# Sch_Sh1.net
KiCad netlist of a schematic drawn in Altium Designer
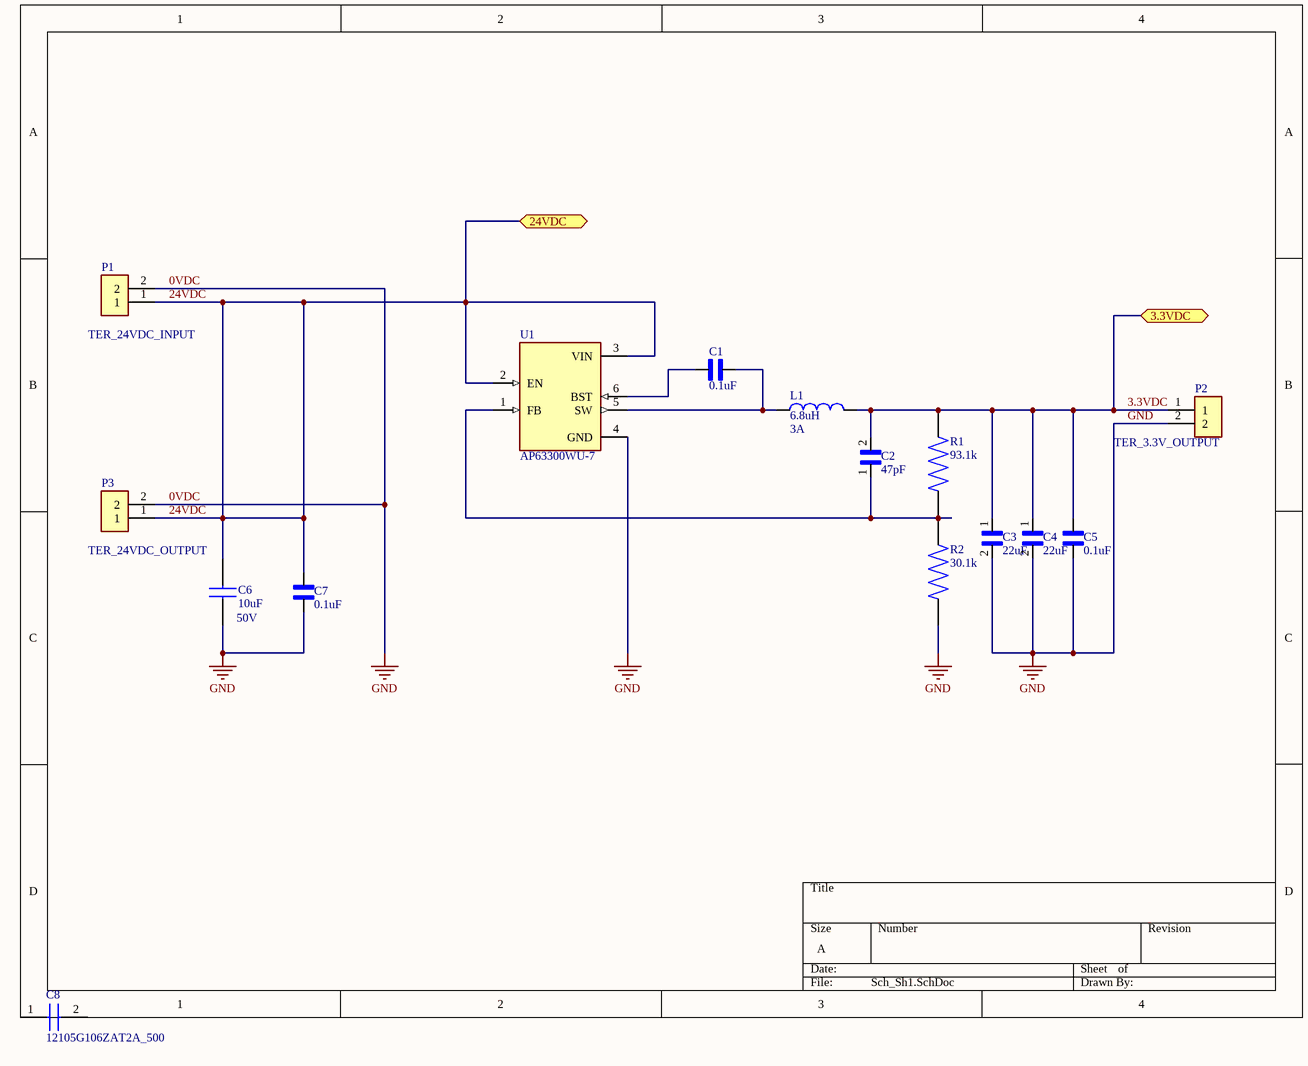
[diagram p0: Sch_Sh1.SchDoc]

(export (version "E")
  (design (tool "Eeschema 10.0.6"))
  (components
    (comp (ref "C1")
      (value "0.1uF")
      (footprint "WCAP-CSGP_885012205086")
      (fields (field (name "MP") "885012205086"))
      (libsource (lib "885012205086") (part "885012205086"))
    )
    (comp (ref "C2")
      (value "47pF")
      (footprint "SnapEDApcb:CAPC2012X145N")
      (description "SMD Capacitor X6S_EIA_ with Capacitance: 10uF Tol. 10%. Rated Voltage: 35Vdc")
      (fields (field (name "MP") "GRM21BC8YA106KE11L") (field (name "MF") "Murata"))
      (libsource (lib "SnapEDAsch") (part "GRM21BC8YA106KE11L"))
    )
    (comp (ref "C3")
      (value "22uF")
      (footprint "CAPC2012X140N")
      (description "22ÂµF Â±20% 25V Ceramic Capacitor X5R 0805 (2012 Metric)")
      (fields (field (name "MF") "Samsung") (field (name "DIGI-KEY_PART_NUMBER") "1276-2908-1-ND"))
      (libsource (lib "CL21A226MAQNNNE") (part "CL21A226MAQNNNE"))
    )
    (comp (ref "C4")
      (value "22uF")
      (footprint "CAPC2012X140N")
      (description "22ÂµF Â±20% 25V Ceramic Capacitor X5R 0805 (2012 Metric)")
      (fields (field (name "MF") "Samsung") (field (name "DIGI-KEY_PART_NUMBER") "1276-2908-1-ND"))
      (libsource (lib "CL21A226MAQNNNE") (part "CL21A226MAQNNNE"))
    )
    (comp (ref "C5")
      (value "0.1uF")
      (footprint "WCAP-CSGP_885012205086")
      (fields (field (name "MP") "885012205086"))
      (libsource (lib "") (part "885012205086_1"))
    )
    (comp (ref "C6")
      (value "10uF")
      (footprint "CAPC3225X290N")
      (description "CAP CER 10UF 50V Y5V 1210")
      (fields
        (field (name "MANUFACTURER_PART_NUMBER") "12105G106ZAT2A/500")
        (field (name "ALTIUM_UNNAMED_1") "50V")
      )
      (libsource (lib "12105G106ZAT2A_500") (part "12105G106ZAT2A_500"))
    )
    (comp (ref "C7")
      (value "0.1uF")
      (footprint "WCAP-CSGP_885012205086")
      (fields (field (name "MP") "885012205086"))
      (libsource (lib "") (part "885012205086_1"))
    )
    (comp (ref "C8")
      (value "12105G106ZAT2A_500")
      (footprint "SamacSys:CAPC3225X290N")
      (description "Capacitor")
      (fields (field (name "MANUFACTURER_PART_NUMBER") "12105G106ZAT2A/500"))
      (libsource (lib "*") (part "12105G106ZAT2A_500"))
    )
    (comp (ref "L1")
      (value "6.8uH")
      (footprint "INDC3225X170N")
      (description "INDUCTOR, 6.8UH, 1.05A, +20%")
      (fields (field (name "MP") "BRL3225T6R8M") (field (name "ALTIUM_UNNAMED_1") "3A"))
      (libsource (lib "BRL3225T6R8M") (part "BRL3225T6R8M"))
    )
    (comp (ref "P1")
      (value "282837-2")
      (footprint "TE_282837-2")
      (description "Connector Terminal Blocks Receptacle 2 Position 5.08mm Solder Straight Thru-Hole 13.5A/Contact")
      (fields (field (name "MF") "TE Connectivity") (field (name "COMMENT_1") "TER_24VDC_INPUT"))
      (libsource (lib "Con_TerminalBlock_2Pin_5.08mm") (part "282837-2"))
    )
    (comp (ref "P2")
      (value "282837-2")
      (footprint "TE_282837-2")
      (description "Connector Terminal Blocks Receptacle 2 Position 5.08mm Solder Straight Thru-Hole 13.5A/Contact")
      (fields (field (name "MF") "TE Connectivity") (field (name "COMMENT_1") "TER_3.3V_OUTPUT"))
      (libsource (lib "") (part "282837-2_1"))
    )
    (comp (ref "P3")
      (value "282837-2")
      (footprint "TE_282837-2")
      (description "Connector Terminal Blocks Receptacle 2 Position 5.08mm Solder Straight Thru-Hole 13.5A/Contact")
      (fields (field (name "MF") "TE Connectivity") (field (name "COMMENT_1") "TER_24VDC_OUTPUT"))
      (libsource (lib "Con_TerminalBlock_2Pin_5.08mm") (part "282837-2"))
    )
    (comp (ref "R1")
      (value "93.1k")
      (footprint "RESC1005X40N")
      (description "Res Thick Film 0402 93.1K Ohm 1% 1/16W Â±100ppm/Â°C Molded SMD Paper T/R")
      (fields (field (name "MP") "RC0402FR-0793K1L"))
      (libsource (lib "RC0402FR-0793K1L") (part "RC0402FR-0793K1L"))
    )
    (comp (ref "R2")
      (value "30.1k")
      (footprint "RES_ERJ2RKF3012X")
      (fields (field (name "MP") "ERJ2RKF3012X"))
      (libsource (lib "ERJ2RKF3012X") (part "ERJ2RKF3012X"))
    )
    (comp (ref "U1")
      (value "AP63300WU-7")
      (footprint "SOT95P280X100-6N")
      (description "Buck Switching Regulator IC Positive Adjustable 0.8V 1 Output 3A SOT-23-6 Thin, TSOT-23-6")
      (fields (field (name "MF") "Diodes Incorporated"))
      (libsource (lib "AP63300WU-7") (part "AP63300WU-7"))
    )
  )
  (nets
    (net (code "1") (name "/3.3VDC") (class "Default")
      (node (ref "C2") (pin "2") (pinfunction "2_2") (pintype "passive"))
      (node (ref "C3") (pin "1") (pinfunction "1_1") (pintype "passive"))
      (node (ref "C4") (pin "1") (pinfunction "1_1") (pintype "passive"))
      (node (ref "C5") (pin "2") (pinfunction "2_2") (pintype "passive"))
      (node (ref "L1") (pin "2") (pinfunction "2_2") (pintype "passive"))
      (node (ref "P2") (pin "1") (pinfunction "1_1") (pintype "passive"))
      (node (ref "R1") (pin "2") (pinfunction "2_2") (pintype "passive"))
    )
    (net (code "2") (name "/24VDC") (class "Default")
      (node (ref "C6") (pin "2") (pinfunction "2_2") (pintype "passive"))
      (node (ref "C7") (pin "2") (pinfunction "2_2") (pintype "passive"))
      (node (ref "P1") (pin "1") (pinfunction "1_1") (pintype "passive"))
      (node (ref "P3") (pin "1") (pinfunction "1_1") (pintype "passive"))
      (node (ref "U1") (pin "2") (pinfunction "EN_2") (pintype "input"))
      (node (ref "U1") (pin "3") (pinfunction "VIN_3") (pintype "power_in"))
    )
    (net (code "3") (name "GND") (class "Default")
      (node (ref "C3") (pin "2") (pinfunction "2_2") (pintype "passive"))
      (node (ref "C4") (pin "2") (pinfunction "2_2") (pintype "passive"))
      (node (ref "C5") (pin "1") (pinfunction "1_1") (pintype "passive"))
      (node (ref "C6") (pin "1") (pinfunction "1_1") (pintype "passive"))
      (node (ref "C7") (pin "1") (pinfunction "1_1") (pintype "passive"))
      (node (ref "P1") (pin "2") (pinfunction "2_2") (pintype "passive"))
      (node (ref "P2") (pin "2") (pinfunction "2_2") (pintype "passive"))
      (node (ref "P3") (pin "2") (pinfunction "2_2") (pintype "passive"))
      (node (ref "R2") (pin "1") (pinfunction "1_1") (pintype "passive"))
      (node (ref "U1") (pin "4") (pinfunction "GND_4") (pintype "power_in"))
    )
    (net (code "4") (name "Net-(U1-BST)") (class "Default")
      (node (ref "C1") (pin "2") (pinfunction "2_2") (pintype "passive"))
      (node (ref "U1") (pin "6") (pinfunction "BST_6") (pintype "input"))
    )
    (net (code "5") (name "Net-(U1-FB)") (class "Default")
      (node (ref "C2") (pin "1") (pinfunction "1_1") (pintype "passive"))
      (node (ref "R1") (pin "1") (pinfunction "1_1") (pintype "passive"))
      (node (ref "R2") (pin "2") (pinfunction "2_2") (pintype "passive"))
      (node (ref "U1") (pin "1") (pinfunction "FB_1") (pintype "input"))
    )
    (net (code "6") (name "Net-(U1-SW)") (class "Default")
      (node (ref "C1") (pin "1") (pinfunction "1_1") (pintype "passive"))
      (node (ref "L1") (pin "1") (pinfunction "1_1") (pintype "passive"))
      (node (ref "U1") (pin "5") (pinfunction "SW_5") (pintype "output"))
    )
    (net (code "7") (name "unconnected-(C8-Pad1)") (class "Default")
      (node (ref "C8") (pin "1") (pinfunction "1_1") (pintype "passive"))
    )
    (net (code "8") (name "unconnected-(C8-Pad2)") (class "Default")
      (node (ref "C8") (pin "2") (pinfunction "2_2") (pintype "passive"))
    )
  )
)
